# USB_FTDI.net
KiCad netlist of a schematic drawn in Altium Designer
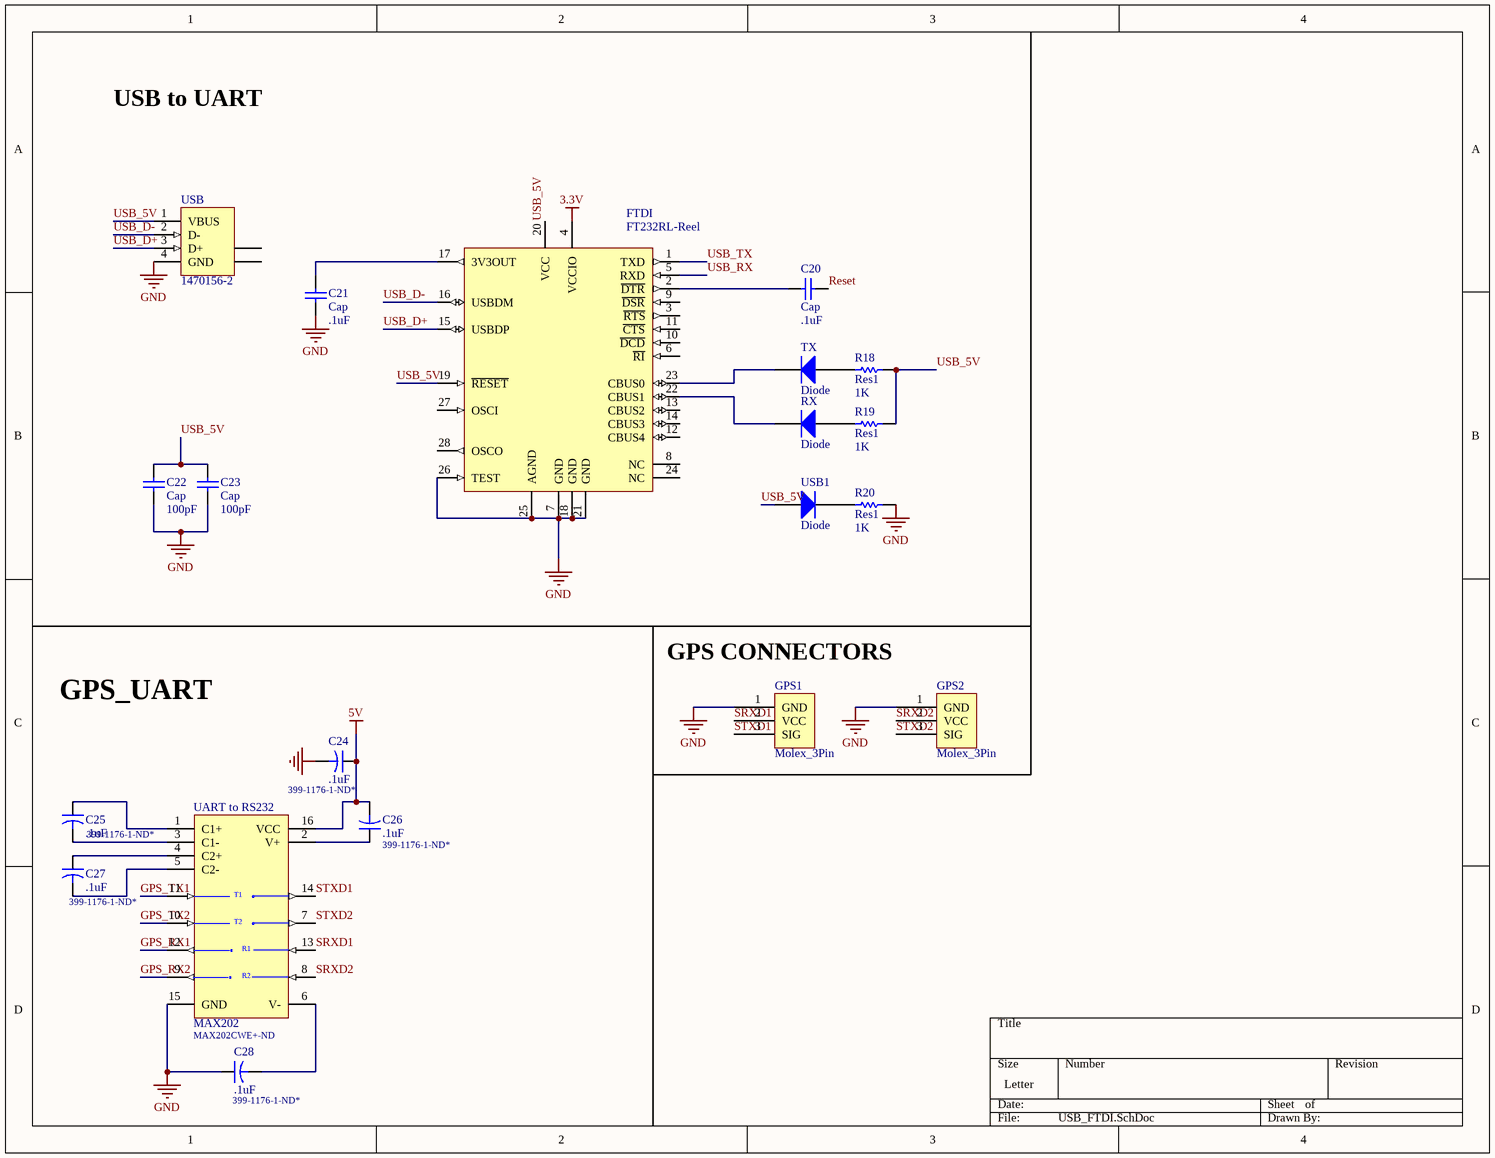
[diagram p0: USB_FTDI.SchDoc]

(export (version "E")
  (design (tool "Eeschema 10.0.6"))
  (components
    (comp (ref "C20")
      (value "Cap")
      (footprint "1608[0603]")
      (description "Capacitor")
      (fields (field (name "ALTIUM_VALUE") ".1uF") (field (name "PUBLISHER") "Altium Limited"))
      (libsource (lib "Miscellaneous Devices") (part "Cap"))
    )
    (comp (ref "C21")
      (value "Cap")
      (footprint "1608[0603]")
      (description "Capacitor")
      (fields (field (name "ALTIUM_VALUE") ".1uF") (field (name "PUBLISHER") "Altium Limited"))
      (libsource (lib "Miscellaneous Devices") (part "Cap"))
    )
    (comp (ref "C22")
      (value "Cap")
      (footprint "1608[0603]")
      (description "Capacitor")
      (fields (field (name "ALTIUM_VALUE") "100pF") (field (name "PUBLISHER") "Altium Limited"))
      (libsource (lib "Miscellaneous Devices") (part "Cap"))
    )
    (comp (ref "C23")
      (value "Cap")
      (footprint "1608[0603]")
      (description "Capacitor")
      (fields (field (name "ALTIUM_VALUE") "100pF") (field (name "PUBLISHER") "Altium Limited"))
      (libsource (lib "Miscellaneous Devices") (part "Cap"))
    )
    (comp (ref "C24") (value ".1uF") (footprint "1608[0603]") (libsource (lib "MowerLib") (part "0805 Cap")))
    (comp (ref "C25") (value ".1uF") (footprint "1608[0603]") (libsource (lib "MowerLib") (part "0805 Cap")))
    (comp (ref "C26") (value ".1uF") (footprint "1608[0603]") (libsource (lib "MowerLib") (part "0805 Cap")))
    (comp (ref "C27") (value ".1uF") (footprint "1608[0603]") (libsource (lib "MowerLib") (part "0805 Cap")))
    (comp (ref "C28") (value ".1uF") (footprint "1608[0603]") (libsource (lib "MowerLib") (part "0805 Cap")))
    (comp (ref "FTDI")
      (value "FT232RL-Reel")
      (footprint "SSOP-28_N")
      (description "USB UART Asynchronous Serial Data Transfer Chip, SSOP-28, Tape and Reel")
      (fields (field (name "PUBLISHER") "Altium Limited"))
      (libsource (lib "FTDI Communication UART") (part "FT232RL-Reel"))
    )
    (comp (ref "GPS1")
      (value "Molex_3Pin")
      (footprint "PCBComponent_1")
      (libsource (lib "Molex_3Pin") (part "Molex_3Pin"))
    )
    (comp (ref "GPS2")
      (value "Molex_3Pin")
      (footprint "PCBComponent_1")
      (libsource (lib "Molex_3Pin") (part "Molex_3Pin"))
    )
    (comp (ref "R18")
      (value "Res1")
      (footprint "1608[0603]")
      (description "Resistor")
      (fields (field (name "ALTIUM_VALUE") "1K") (field (name "PUBLISHER") "Altium Limited"))
      (libsource (lib "Miscellaneous Devices") (part "Res1"))
    )
    (comp (ref "R19")
      (value "Res1")
      (footprint "1608[0603]")
      (description "Resistor")
      (fields (field (name "ALTIUM_VALUE") "1K") (field (name "PUBLISHER") "Altium Limited"))
      (libsource (lib "Miscellaneous Devices") (part "Res1"))
    )
    (comp (ref "R20")
      (value "Res1")
      (footprint "1608[0603]")
      (description "Resistor")
      (fields (field (name "ALTIUM_VALUE") "1K") (field (name "PUBLISHER") "Altium Limited"))
      (libsource (lib "Miscellaneous Devices") (part "Res1"))
    )
    (comp (ref "RX")
      (value "Diode")
      (footprint "1608[0603]")
      (description "Default Diode")
      (fields (field (name "PUBLISHER") "Altium Limited"))
      (libsource (lib "Miscellaneous Devices") (part "Diode"))
    )
    (comp (ref "TX")
      (value "Diode")
      (footprint "1608[0603]")
      (description "Default Diode")
      (fields (field (name "PUBLISHER") "Altium Limited"))
      (libsource (lib "Miscellaneous Devices") (part "Diode"))
    )
    (comp (ref "UART to RS232")
      (value "MAX202")
      (footprint "WSO16_N")
      (description "+5V RS-232 Transceiver with 0.1µF External Capacitor (Digi-Key#: MAX202CWE+-ND)")
      (fields (field (name "PUBLISHER") "Altium Limited"))
      (libsource (lib "MowerLib") (part "MAX202CWE"))
    )
    (comp (ref "USB")
      (value "1470156-2")
      (footprint "1470156")
      (description "USB 1.1, Right Angle, Thru-Hole, B Type, Receptacle, 4 Position, Black")
      (fields (field (name "PUBLISHER") "Altium Limited"))
      (libsource (lib "AMP Serial Bus USB") (part "1470156-2"))
    )
    (comp (ref "USB1")
      (value "Diode")
      (footprint "1608[0603]")
      (description "Default Diode")
      (fields (field (name "PUBLISHER") "Altium Limited"))
      (libsource (lib "Miscellaneous Devices") (part "Diode"))
    )
  )
  (nets
    (net (code "1") (name "/GPS_RX1") (class "Default")
      (node (ref "UART to RS232") (pin "12") (pinfunction "R1OUT_12") (pintype "output"))
    )
    (net (code "2") (name "/GPS_RX2") (class "Default")
      (node (ref "UART to RS232") (pin "9") (pinfunction "R2OUT_9") (pintype "output"))
    )
    (net (code "3") (name "/GPS_TX1") (class "Default")
      (node (ref "UART to RS232") (pin "11") (pinfunction "T1IN_11") (pintype "input"))
    )
    (net (code "4") (name "/GPS_TX2") (class "Default")
      (node (ref "UART to RS232") (pin "10") (pinfunction "T2IN_10") (pintype "input"))
    )
    (net (code "5") (name "/Reset") (class "Default")
      (node (ref "C20") (pin "1") (pinfunction "1_1") (pintype "passive"))
    )
    (net (code "6") (name "/SRXD1") (class "Default")
      (node (ref "GPS1") (pin "2") (pinfunction "VCC_2") (pintype "power_in"))
      (node (ref "UART to RS232") (pin "13") (pinfunction "R1IN_13") (pintype "input"))
    )
    (net (code "7") (name "/SRXD2") (class "Default")
      (node (ref "GPS2") (pin "2") (pinfunction "VCC_2") (pintype "power_in"))
      (node (ref "UART to RS232") (pin "8") (pinfunction "R2IN_8") (pintype "input"))
    )
    (net (code "8") (name "/STXD1") (class "Default")
      (node (ref "GPS1") (pin "3") (pinfunction "SIG_3") (pintype "power_in"))
      (node (ref "UART to RS232") (pin "14") (pinfunction "T1OUT_14") (pintype "output"))
    )
    (net (code "9") (name "/STXD2") (class "Default")
      (node (ref "GPS2") (pin "3") (pinfunction "SIG_3") (pintype "power_in"))
      (node (ref "UART to RS232") (pin "7") (pinfunction "T2OUT_7") (pintype "output"))
    )
    (net (code "10") (name "/USB_5V") (class "Default")
      (node (ref "C22") (pin "2") (pinfunction "2_2") (pintype "passive"))
      (node (ref "C23") (pin "2") (pinfunction "2_2") (pintype "passive"))
      (node (ref "FTDI") (pin "19") (pinfunction "~{RESET}_19") (pintype "input"))
      (node (ref "FTDI") (pin "20") (pinfunction "VCC_20") (pintype "power_in"))
      (node (ref "R18") (pin "2") (pinfunction "2_2") (pintype "passive"))
      (node (ref "R19") (pin "2") (pinfunction "2_2") (pintype "passive"))
      (node (ref "USB") (pin "1") (pinfunction "VBUS_1") (pintype "power_in"))
      (node (ref "USB1") (pin "1") (pinfunction "A_1") (pintype "passive"))
    )
    (net (code "11") (name "/USB_D+") (class "Default")
      (node (ref "FTDI") (pin "15") (pinfunction "USBDP_15") (pintype "bidirectional"))
      (node (ref "USB") (pin "3") (pinfunction "D+_3") (pintype "input"))
    )
    (net (code "12") (name "/USB_D-") (class "Default")
      (node (ref "FTDI") (pin "16") (pinfunction "USBDM_16") (pintype "bidirectional"))
      (node (ref "USB") (pin "2") (pinfunction "D-_2") (pintype "input"))
    )
    (net (code "13") (name "/USB_RX") (class "Default")
      (node (ref "FTDI") (pin "5") (pinfunction "RXD_5") (pintype "input"))
    )
    (net (code "14") (name "/USB_TX") (class "Default")
      (node (ref "FTDI") (pin "1") (pinfunction "TXD_1") (pintype "output"))
    )
    (net (code "15") (name "3.3V") (class "Default")
      (node (ref "FTDI") (pin "4") (pinfunction "VCCIO_4") (pintype "power_in"))
    )
    (net (code "16") (name "5V") (class "Default")
      (node (ref "C24") (pin "1") (pinfunction "1_1") (pintype "passive"))
      (node (ref "C26") (pin "2") (pinfunction "2_2") (pintype "passive"))
      (node (ref "UART to RS232") (pin "16") (pinfunction "VCC_16") (pintype "power_in"))
    )
    (net (code "17") (name "GND") (class "Default")
      (node (ref "C21") (pin "1") (pinfunction "1_1") (pintype "passive"))
      (node (ref "C22") (pin "1") (pinfunction "1_1") (pintype "passive"))
      (node (ref "C23") (pin "1") (pinfunction "1_1") (pintype "passive"))
      (node (ref "C24") (pin "2") (pinfunction "2_2") (pintype "passive"))
      (node (ref "C28") (pin "1") (pinfunction "1_1") (pintype "passive"))
      (node (ref "FTDI") (pin "18") (pinfunction "GND_18") (pintype "power_in"))
      (node (ref "FTDI") (pin "21") (pinfunction "GND_21") (pintype "power_in"))
      (node (ref "FTDI") (pin "25") (pinfunction "AGND_25") (pintype "power_in"))
      (node (ref "FTDI") (pin "26") (pinfunction "TEST_26") (pintype "input"))
      (node (ref "FTDI") (pin "7") (pinfunction "GND_7") (pintype "power_in"))
      (node (ref "GPS1") (pin "1") (pinfunction "GND_1") (pintype "power_in"))
      (node (ref "GPS2") (pin "1") (pinfunction "GND_1") (pintype "power_in"))
      (node (ref "R20") (pin "2") (pinfunction "2_2") (pintype "passive"))
      (node (ref "UART to RS232") (pin "15") (pinfunction "GND_15") (pintype "power_in"))
      (node (ref "USB") (pin "4") (pinfunction "GND_4") (pintype "power_in"))
    )
    (net (code "18") (name "Net-(FTDI-3V3OUT)") (class "Default")
      (node (ref "C21") (pin "2") (pinfunction "2_2") (pintype "passive"))
      (node (ref "FTDI") (pin "17") (pinfunction "3V3OUT_17") (pintype "output"))
    )
    (net (code "19") (name "Net-(FTDI-CBUS0)") (class "Default")
      (node (ref "FTDI") (pin "23") (pinfunction "CBUS0_23") (pintype "bidirectional"))
      (node (ref "TX") (pin "2") (pinfunction "K_2") (pintype "passive"))
    )
    (net (code "20") (name "Net-(FTDI-CBUS1)") (class "Default")
      (node (ref "FTDI") (pin "22") (pinfunction "CBUS1_22") (pintype "bidirectional"))
      (node (ref "RX") (pin "2") (pinfunction "K_2") (pintype "passive"))
    )
    (net (code "21") (name "Net-(FTDI-~{DTR})") (class "Default")
      (node (ref "C20") (pin "2") (pinfunction "2_2") (pintype "passive"))
      (node (ref "FTDI") (pin "2") (pinfunction "~{DTR}_2") (pintype "output"))
    )
    (net (code "22") (name "Net-(RX-A)") (class "Default")
      (node (ref "R19") (pin "1") (pinfunction "1_1") (pintype "passive"))
      (node (ref "RX") (pin "1") (pinfunction "A_1") (pintype "passive"))
    )
    (net (code "23") (name "Net-(TX-A)") (class "Default")
      (node (ref "R18") (pin "1") (pinfunction "1_1") (pintype "passive"))
      (node (ref "TX") (pin "1") (pinfunction "A_1") (pintype "passive"))
    )
    (net (code "24") (name "Net-(UART to RS232-C1+)") (class "Default")
      (node (ref "C25") (pin "1") (pinfunction "1_1") (pintype "passive"))
      (node (ref "UART to RS232") (pin "1") (pinfunction "C1+_1") (pintype "passive"))
    )
    (net (code "25") (name "Net-(UART to RS232-C1-)") (class "Default")
      (node (ref "C25") (pin "2") (pinfunction "2_2") (pintype "passive"))
      (node (ref "UART to RS232") (pin "3") (pinfunction "C1-_3") (pintype "passive"))
    )
    (net (code "26") (name "Net-(UART to RS232-C2+)") (class "Default")
      (node (ref "C27") (pin "1") (pinfunction "1_1") (pintype "passive"))
      (node (ref "UART to RS232") (pin "4") (pinfunction "C2+_4") (pintype "passive"))
    )
    (net (code "27") (name "Net-(UART to RS232-C2-)") (class "Default")
      (node (ref "C27") (pin "2") (pinfunction "2_2") (pintype "passive"))
      (node (ref "UART to RS232") (pin "5") (pinfunction "C2-_5") (pintype "passive"))
    )
    (net (code "28") (name "Net-(UART to RS232-V+)") (class "Default")
      (node (ref "C26") (pin "1") (pinfunction "1_1") (pintype "passive"))
      (node (ref "UART to RS232") (pin "2") (pinfunction "V+_2") (pintype "power_in"))
    )
    (net (code "29") (name "Net-(UART to RS232-V-)") (class "Default")
      (node (ref "C28") (pin "2") (pinfunction "2_2") (pintype "passive"))
      (node (ref "UART to RS232") (pin "6") (pinfunction "V-_6") (pintype "power_in"))
    )
    (net (code "30") (name "Net-(USB1-K)") (class "Default")
      (node (ref "R20") (pin "1") (pinfunction "1_1") (pintype "passive"))
      (node (ref "USB1") (pin "2") (pinfunction "K_2") (pintype "passive"))
    )
    (net (code "31") (name "unconnected-(FTDI-CBUS2-Pad13)") (class "Default")
      (node (ref "FTDI") (pin "13") (pinfunction "CBUS2_13") (pintype "bidirectional"))
    )
    (net (code "32") (name "unconnected-(FTDI-CBUS3-Pad14)") (class "Default")
      (node (ref "FTDI") (pin "14") (pinfunction "CBUS3_14") (pintype "bidirectional"))
    )
    (net (code "33") (name "unconnected-(FTDI-CBUS4-Pad12)") (class "Default")
      (node (ref "FTDI") (pin "12") (pinfunction "CBUS4_12") (pintype "bidirectional"))
    )
    (net (code "34") (name "unconnected-(FTDI-NC-Pad8)") (class "Default")
      (node (ref "FTDI") (pin "8") (pinfunction "NC_8") (pintype "passive"))
    )
    (net (code "35") (name "unconnected-(FTDI-NC-Pad24)") (class "Default")
      (node (ref "FTDI") (pin "24") (pinfunction "NC_24") (pintype "passive"))
    )
    (net (code "36") (name "unconnected-(FTDI-OSCI-Pad27)") (class "Default")
      (node (ref "FTDI") (pin "27") (pinfunction "OSCI_27") (pintype "input"))
    )
    (net (code "37") (name "unconnected-(FTDI-OSCO-Pad28)") (class "Default")
      (node (ref "FTDI") (pin "28") (pinfunction "OSCO_28") (pintype "output"))
    )
    (net (code "38") (name "unconnected-(FTDI-~{CTS}-Pad11)") (class "Default")
      (node (ref "FTDI") (pin "11") (pinfunction "~{CTS}_11") (pintype "input"))
    )
    (net (code "39") (name "unconnected-(FTDI-~{DCD}-Pad10)") (class "Default")
      (node (ref "FTDI") (pin "10") (pinfunction "~{DCD}_10") (pintype "input"))
    )
    (net (code "40") (name "unconnected-(FTDI-~{DSR}-Pad9)") (class "Default")
      (node (ref "FTDI") (pin "9") (pinfunction "~{DSR}_9") (pintype "input"))
    )
    (net (code "41") (name "unconnected-(FTDI-~{RI}-Pad6)") (class "Default")
      (node (ref "FTDI") (pin "6") (pinfunction "~{RI}_6") (pintype "input"))
    )
    (net (code "42") (name "unconnected-(FTDI-~{RTS}-Pad3)") (class "Default")
      (node (ref "FTDI") (pin "3") (pinfunction "~{RTS}_3") (pintype "output"))
    )
    (net (code "43") (name "unconnected-(USB-SHLD-Pad5)") (class "Default")
      (node (ref "USB") (pin "5") (pinfunction "SHLD_5") (pintype "passive"))
    )
    (net (code "44") (name "unconnected-(USB-SHLD-Pad6)") (class "Default")
      (node (ref "USB") (pin "6") (pinfunction "SHLD_6") (pintype "passive"))
    )
  )
)
